# ProSense.net
KiCad netlist of a schematic drawn in EAGLE
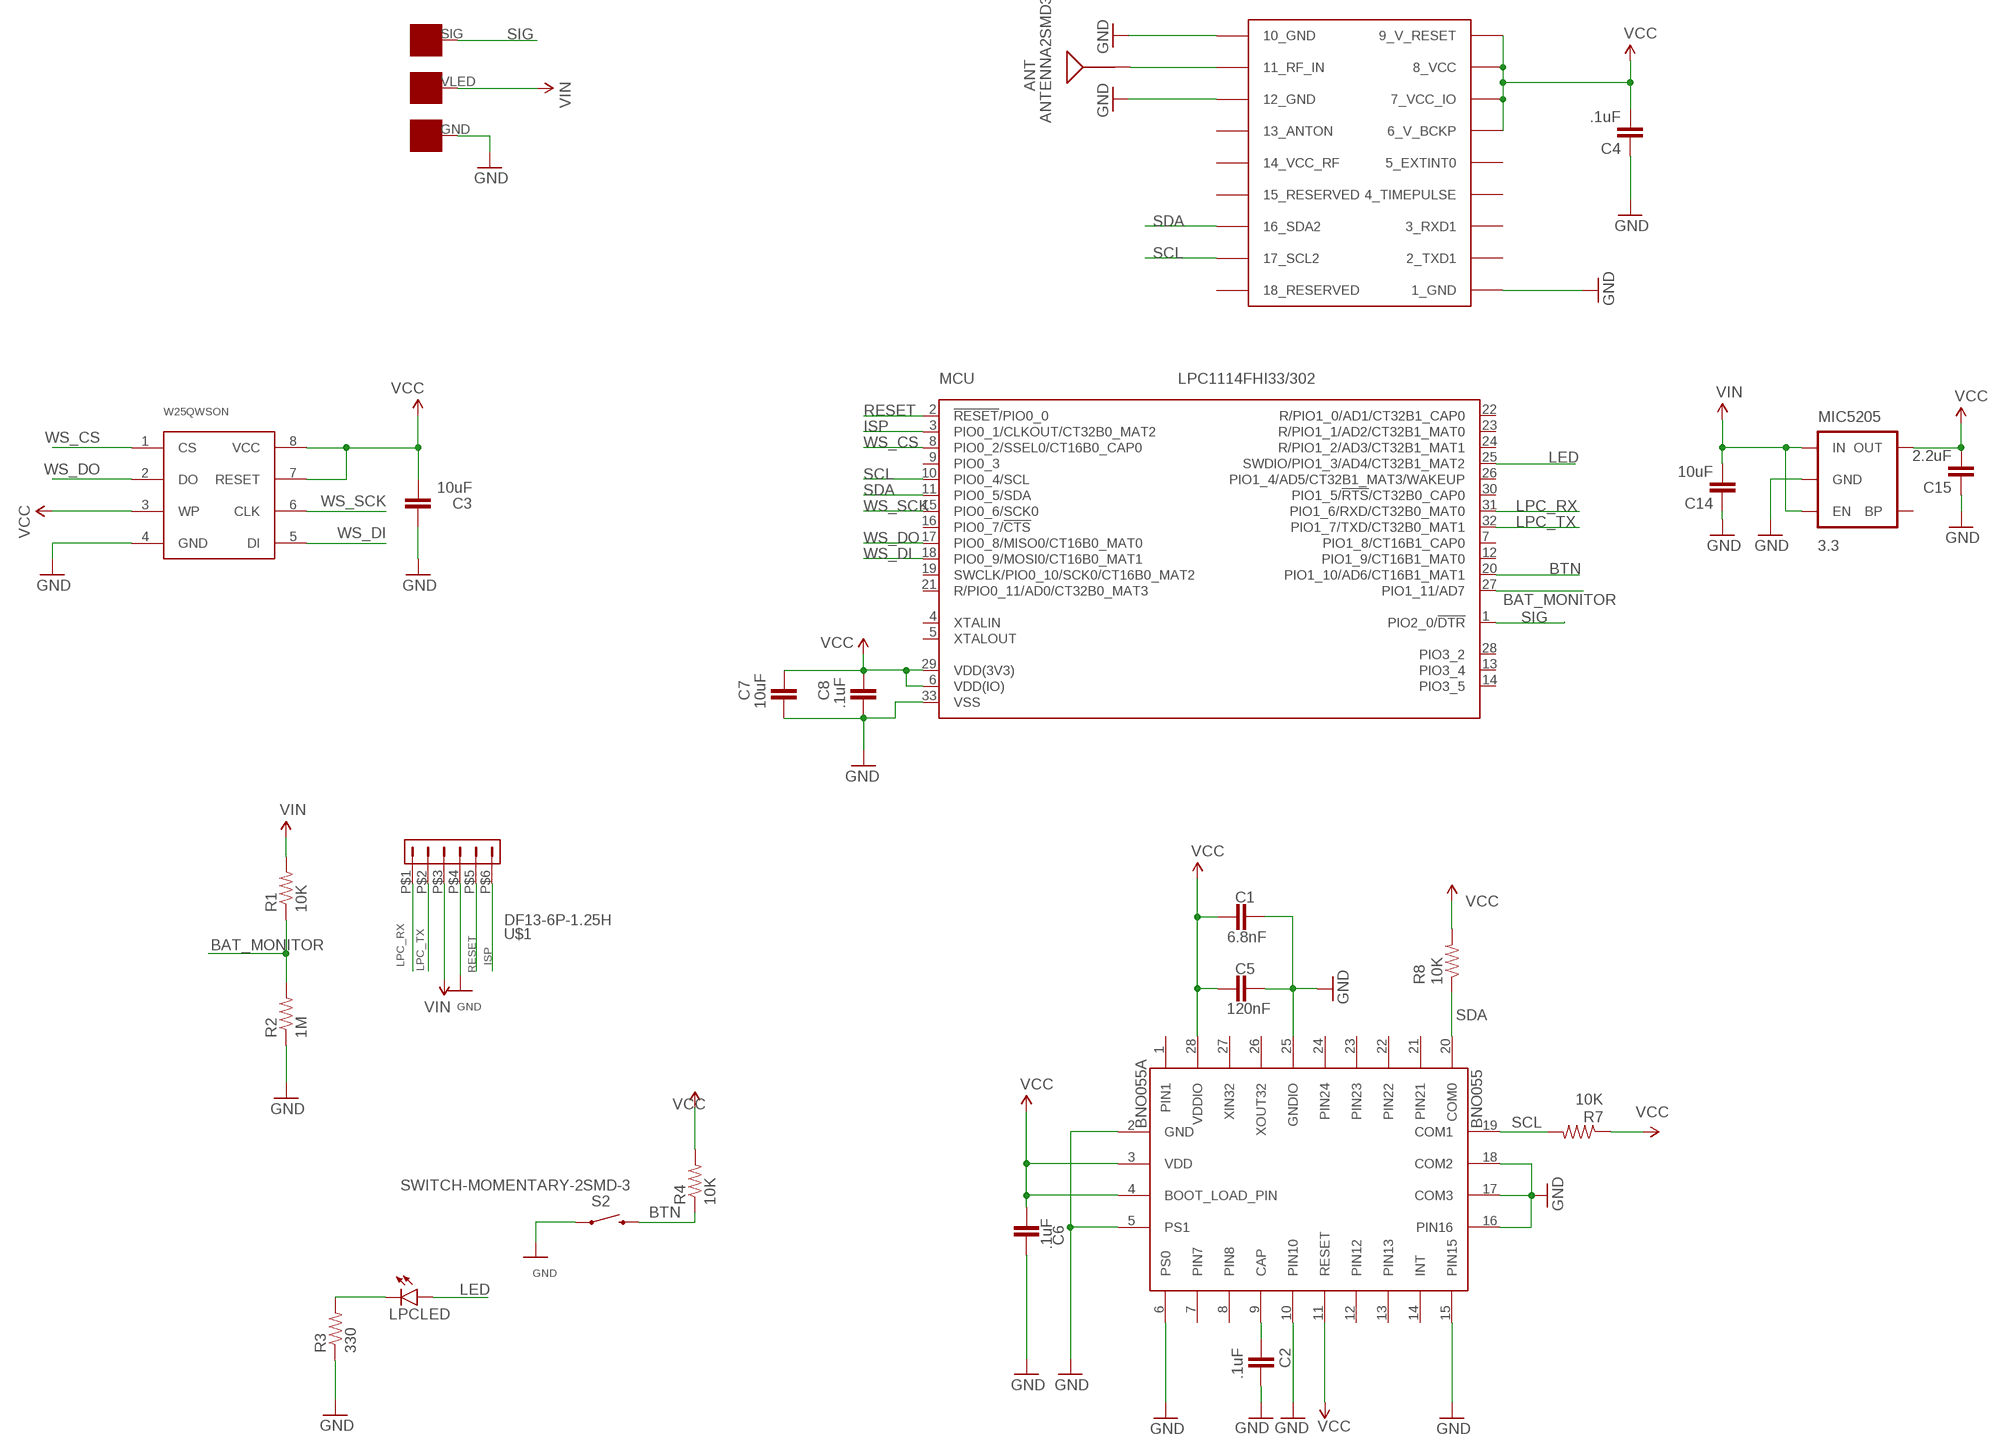
[diagram p0: schematic, sheet 1]

(export (version "E")
  (design (tool "Eeschema 10.0.6"))
  (components
    (comp (ref "ANT")
      (value "ANTENNA2SMD3")
      (footprint "eagle-import:ANTENNA-CHIP4")
      (libsource (lib "eagle-import") (part "ANTENNA2SMD3"))
    )
    (comp (ref "BNO055")
      (value "BNO055A")
      (footprint "eagle-import:BNO055")
      (libsource (lib "eagle-import") (part "BNO055A"))
    )
    (comp (ref "C1")
      (value "6.8nF")
      (footprint "eagle-import:0603-CAP")
      (libsource (lib "eagle-import") (part "CAP0603-CAP"))
    )
    (comp (ref "C2")
      (value ".1uF")
      (footprint "eagle-import:0603-CAP")
      (libsource (lib "eagle-import") (part "CAP0603-CAP"))
    )
    (comp (ref "C3")
      (value "10uF")
      (footprint "eagle-import:0603-CAP")
      (libsource (lib "eagle-import") (part "CAP0603-CAP"))
    )
    (comp (ref "C4")
      (value ".1uF")
      (footprint "eagle-import:0603-CAP")
      (libsource (lib "eagle-import") (part "CAP0603-CAP"))
    )
    (comp (ref "C5")
      (value "120nF")
      (footprint "eagle-import:0603-CAP")
      (libsource (lib "eagle-import") (part "CAP0603-CAP"))
    )
    (comp (ref "C6")
      (value ".1uF")
      (footprint "eagle-import:0603-CAP")
      (libsource (lib "eagle-import") (part "CAP0603-CAP"))
    )
    (comp (ref "C7")
      (value "10uF")
      (footprint "eagle-import:0603-CAP")
      (libsource (lib "eagle-import") (part "CAP0603-CAP"))
    )
    (comp (ref "C8")
      (value ".1uF")
      (footprint "eagle-import:0603-CAP")
      (libsource (lib "eagle-import") (part "CAP0603-CAP"))
    )
    (comp (ref "C14")
      (value "10uF")
      (footprint "eagle-import:0603-CAP")
      (libsource (lib "eagle-import") (part "CAP0603-CAP"))
    )
    (comp (ref "C15")
      (value "2.2uF")
      (footprint "eagle-import:0603-CAP")
      (libsource (lib "eagle-import") (part "CAP0603-CAP"))
    )
    (comp (ref "LPCLED")
      (value "LED0603")
      (footprint "eagle-import:LED-0603")
      (libsource (lib "eagle-import") (part "LED0603"))
    )
    (comp (ref "MCU")
      (value "LPC1114FHI33/302")
      (footprint "eagle-import:SOT617-3")
      (libsource (lib "eagle-import") (part "LPC1114FHI33/302"))
    )
    (comp (ref "MIC5205")
      (value "3.3")
      (footprint "eagle-import:SOT23-5")
      (libsource (lib "eagle-import") (part "MIC52053.3V"))
    )
    (comp (ref "R1")
      (value "10K")
      (footprint "eagle-import:0603-RES")
      (libsource (lib "eagle-import") (part "RESISTOR0603-RES"))
    )
    (comp (ref "R2")
      (value "1M")
      (footprint "eagle-import:0603-RES")
      (libsource (lib "eagle-import") (part "RESISTOR0603-RES"))
    )
    (comp (ref "R3")
      (value "330")
      (footprint "eagle-import:0603-RES")
      (libsource (lib "eagle-import") (part "RESISTOR0603-RES"))
    )
    (comp (ref "R4")
      (value "10K")
      (footprint "eagle-import:0603-RES")
      (libsource (lib "eagle-import") (part "RESISTOR0603-RES"))
    )
    (comp (ref "R7")
      (value "10K")
      (footprint "eagle-import:0603-RES")
      (libsource (lib "eagle-import") (part "RESISTOR0603-RES"))
    )
    (comp (ref "R8")
      (value "10K")
      (footprint "eagle-import:0603-RES")
      (libsource (lib "eagle-import") (part "RESISTOR0603-RES"))
    )
    (comp (ref "S2")
      (value "SWITCH-MOMENTARY-2SMD-3")
      (footprint "eagle-import:TACTILE_SWITCH_SMD-3")
      (libsource (lib "eagle-import") (part "SWITCH-MOMENTARY-2SMD-3"))
    )
    (comp (ref "U$1")
      (value "DF13-6P-1.25H")
      (footprint "eagle-import:DF13A-6P-1.25H")
      (libsource (lib "eagle-import") (part "DF13-6P-1.25H"))
    )
    (comp (ref "U$2")
      (value "UBLOX_MAX")
      (footprint "eagle-import:UBLOX_MAX")
      (libsource (lib "eagle-import") (part "UBLOX_MAX"))
    )
    (comp (ref "U$4")
      (value "CON")
      (footprint "eagle-import:COPPER-PAD")
      (libsource (lib "eagle-import") (part "CON"))
    )
    (comp (ref "W25QWSON")
      (value "W25Q128FVWSON")
      (footprint "eagle-import:WSON-8-PAD")
      (libsource (lib "eagle-import") (part "W25Q128FVWSON"))
    )
  )
  (nets
    (net (code "1") (name "/BAT_MONITOR") (class "Default")
      (node (ref "MCU") (pin "27") (pinfunction "PIO1_11/AD7_27") (pintype "bidirectional"))
      (node (ref "R1") (pin "1") (pinfunction "1_1") (pintype "passive"))
      (node (ref "R2") (pin "2") (pinfunction "2_2") (pintype "passive"))
    )
    (net (code "2") (name "/BTN") (class "Default")
      (node (ref "MCU") (pin "20") (pinfunction "PIO1_10/AD6/CT16B1_MAT1_20") (pintype "bidirectional"))
      (node (ref "R4") (pin "1") (pinfunction "1_1") (pintype "passive"))
      (node (ref "S2") (pin "4") (pinfunction "2_4") (pintype "passive"))
    )
    (net (code "3") (name "/ISP") (class "Default")
      (node (ref "MCU") (pin "3") (pinfunction "PIO0_1/CLKOUT/CT32B0_MAT2_3") (pintype "bidirectional"))
      (node (ref "U$1") (pin "P$6") (pinfunction "6_P$6") (pintype "passive"))
    )
    (net (code "4") (name "/LED") (class "Default")
      (node (ref "LPCLED") (pin "A") (pinfunction "A_A") (pintype "passive"))
      (node (ref "MCU") (pin "25") (pinfunction "SWDIO/PIO1_3/AD4/CT32B1_MAT2_25") (pintype "bidirectional"))
    )
    (net (code "5") (name "/LPC_RX") (class "Default")
      (node (ref "MCU") (pin "31") (pinfunction "PIO1_6/RXD/CT32B0_MAT0_31") (pintype "bidirectional"))
      (node (ref "U$1") (pin "P$1") (pinfunction "1_P$1") (pintype "passive"))
    )
    (net (code "6") (name "/LPC_TX") (class "Default")
      (node (ref "MCU") (pin "32") (pinfunction "PIO1_7/TXD/CT32B0_MAT1_32") (pintype "bidirectional"))
      (node (ref "U$1") (pin "P$2") (pinfunction "2_P$2") (pintype "passive"))
    )
    (net (code "7") (name "/RESET") (class "Default")
      (node (ref "MCU") (pin "2") (pinfunction "~{RESET}/PIO0_0_2") (pintype "bidirectional"))
      (node (ref "U$1") (pin "P$5") (pinfunction "5_P$5") (pintype "passive"))
    )
    (net (code "8") (name "/SCL") (class "Default")
      (node (ref "BNO055") (pin "19") (pinfunction "COM1_19") (pintype "bidirectional"))
      (node (ref "MCU") (pin "10") (pinfunction "PIO0_4/SCL_10") (pintype "bidirectional"))
      (node (ref "R7") (pin "2") (pinfunction "2_2") (pintype "passive"))
      (node (ref "U$2") (pin "17_SCL2") (pinfunction "17_SCL2_17_SCL2") (pintype "bidirectional"))
    )
    (net (code "9") (name "/SDA") (class "Default")
      (node (ref "BNO055") (pin "20") (pinfunction "COM0_20") (pintype "bidirectional"))
      (node (ref "MCU") (pin "11") (pinfunction "PIO0_5/SDA_11") (pintype "bidirectional"))
      (node (ref "R8") (pin "1") (pinfunction "1_1") (pintype "passive"))
      (node (ref "U$2") (pin "16_SDA2") (pinfunction "16_SDA2_16_SDA2") (pintype "bidirectional"))
    )
    (net (code "10") (name "/SIG") (class "Default")
      (node (ref "MCU") (pin "1") (pinfunction "PIO2_0/~{DTR}_1") (pintype "bidirectional"))
      (node (ref "U$4") (pin "SIG") (pinfunction "SIG_SIG") (pintype "bidirectional"))
    )
    (net (code "11") (name "/WS_CS") (class "Default")
      (node (ref "MCU") (pin "8") (pinfunction "PIO0_2/SSEL0/CT16B0_CAP0_8") (pintype "bidirectional"))
      (node (ref "W25QWSON") (pin "1") (pinfunction "CS_1") (pintype "input"))
    )
    (net (code "12") (name "/WS_DI") (class "Default")
      (node (ref "MCU") (pin "18") (pinfunction "PIO0_9/MOSI0/CT16B0_MAT1_18") (pintype "bidirectional"))
      (node (ref "W25QWSON") (pin "5") (pinfunction "DI_5") (pintype "input"))
    )
    (net (code "13") (name "/WS_DO") (class "Default")
      (node (ref "MCU") (pin "17") (pinfunction "PIO0_8/MISO0/CT16B0_MAT0_17") (pintype "bidirectional"))
      (node (ref "W25QWSON") (pin "2") (pinfunction "DO_2") (pintype "output"))
    )
    (net (code "14") (name "/WS_SCK") (class "Default")
      (node (ref "MCU") (pin "15") (pinfunction "PIO0_6/SCK0_15") (pintype "bidirectional"))
      (node (ref "W25QWSON") (pin "6") (pinfunction "CLK_6") (pintype "input"))
    )
    (net (code "15") (name "GND") (class "Default")
      (node (ref "BNO055") (pin "10") (pinfunction "PIN10_10") (pintype "bidirectional"))
      (node (ref "BNO055") (pin "15") (pinfunction "PIN15_15") (pintype "bidirectional"))
      (node (ref "BNO055") (pin "16") (pinfunction "PIN16_16") (pintype "bidirectional"))
      (node (ref "BNO055") (pin "17") (pinfunction "COM3_17") (pintype "bidirectional"))
      (node (ref "BNO055") (pin "18") (pinfunction "COM2_18") (pintype "bidirectional"))
      (node (ref "BNO055") (pin "2") (pinfunction "GND_2") (pintype "bidirectional"))
      (node (ref "BNO055") (pin "25") (pinfunction "GNDIO_25") (pintype "bidirectional"))
      (node (ref "BNO055") (pin "5") (pinfunction "PS1_5") (pintype "bidirectional"))
      (node (ref "BNO055") (pin "6") (pinfunction "PS0_6") (pintype "bidirectional"))
      (node (ref "C1") (pin "1") (pinfunction "1_1") (pintype "passive"))
      (node (ref "C14") (pin "1") (pinfunction "1_1") (pintype "passive"))
      (node (ref "C15") (pin "1") (pinfunction "1_1") (pintype "passive"))
      (node (ref "C2") (pin "1") (pinfunction "1_1") (pintype "passive"))
      (node (ref "C3") (pin "1") (pinfunction "1_1") (pintype "passive"))
      (node (ref "C4") (pin "1") (pinfunction "1_1") (pintype "passive"))
      (node (ref "C5") (pin "1") (pinfunction "1_1") (pintype "passive"))
      (node (ref "C6") (pin "2") (pinfunction "2_2") (pintype "passive"))
      (node (ref "C7") (pin "2") (pinfunction "2_2") (pintype "passive"))
      (node (ref "C8") (pin "2") (pinfunction "2_2") (pintype "passive"))
      (node (ref "MCU") (pin "33") (pinfunction "VSS_33") (pintype "power_in"))
      (node (ref "MIC5205") (pin "2") (pinfunction "GND_2") (pintype "input"))
      (node (ref "R2") (pin "1") (pinfunction "1_1") (pintype "passive"))
      (node (ref "R3") (pin "1") (pinfunction "1_1") (pintype "passive"))
      (node (ref "S2") (pin "1") (pinfunction "1_1") (pintype "passive"))
      (node (ref "U$1") (pin "P$4") (pinfunction "4_P$4") (pintype "passive"))
      (node (ref "U$2") (pin "10_GND") (pinfunction "10_GND_10_GND") (pintype "power_in"))
      (node (ref "U$2") (pin "12_GND") (pinfunction "12_GND_12_GND") (pintype "power_in"))
      (node (ref "U$2") (pin "1_GND") (pinfunction "1_GND_1_GND") (pintype "power_in"))
      (node (ref "U$4") (pin "GND") (pinfunction "GND_GND") (pintype "bidirectional"))
      (node (ref "W25QWSON") (pin "4") (pinfunction "GND_4") (pintype "power_in"))
    )
    (net (code "16") (name "Net-(ANT-SIGNAL)") (class "Default")
      (node (ref "ANT") (pin "SIG") (pinfunction "SIGNAL_SIG") (pintype "bidirectional"))
      (node (ref "U$2") (pin "11_RF_IN") (pinfunction "11_RF_IN_11_RF_IN") (pintype "bidirectional"))
    )
    (net (code "17") (name "Net-(BNO055-CAP)") (class "Default")
      (node (ref "BNO055") (pin "9") (pinfunction "CAP_9") (pintype "bidirectional"))
      (node (ref "C2") (pin "2") (pinfunction "2_2") (pintype "passive"))
    )
    (net (code "18") (name "Net-(LPCLED-PadC)") (class "Default")
      (node (ref "LPCLED") (pin "C") (pinfunction "C_C") (pintype "passive"))
      (node (ref "R3") (pin "2") (pinfunction "2_2") (pintype "passive"))
    )
    (net (code "19") (name "VCC") (class "Default")
      (node (ref "BNO055") (pin "11") (pinfunction "RESET_11") (pintype "bidirectional"))
      (node (ref "BNO055") (pin "28") (pinfunction "VDDIO_28") (pintype "bidirectional"))
      (node (ref "BNO055") (pin "3") (pinfunction "VDD_3") (pintype "bidirectional"))
      (node (ref "BNO055") (pin "4") (pinfunction "BOOT_LOAD_PIN_4") (pintype "bidirectional"))
      (node (ref "C1") (pin "2") (pinfunction "2_2") (pintype "passive"))
      (node (ref "C15") (pin "2") (pinfunction "2_2") (pintype "passive"))
      (node (ref "C3") (pin "2") (pinfunction "2_2") (pintype "passive"))
      (node (ref "C4") (pin "2") (pinfunction "2_2") (pintype "passive"))
      (node (ref "C5") (pin "2") (pinfunction "2_2") (pintype "passive"))
      (node (ref "C6") (pin "1") (pinfunction "1_1") (pintype "passive"))
      (node (ref "C7") (pin "1") (pinfunction "1_1") (pintype "passive"))
      (node (ref "C8") (pin "1") (pinfunction "1_1") (pintype "passive"))
      (node (ref "MCU") (pin "29") (pinfunction "VDD(3V3)_29") (pintype "power_in"))
      (node (ref "MCU") (pin "6") (pinfunction "VDD(IO)_6") (pintype "power_in"))
      (node (ref "MIC5205") (pin "5") (pinfunction "OUT_5") (pintype "passive"))
      (node (ref "R4") (pin "2") (pinfunction "2_2") (pintype "passive"))
      (node (ref "R7") (pin "1") (pinfunction "1_1") (pintype "passive"))
      (node (ref "R8") (pin "2") (pinfunction "2_2") (pintype "passive"))
      (node (ref "U$2") (pin "6_V_BCKP") (pinfunction "6_V_BCKP_6_V_BCKP") (pintype "bidirectional"))
      (node (ref "U$2") (pin "7_VCC_IO") (pinfunction "7_VCC_IO_7_VCC_IO") (pintype "power_in"))
      (node (ref "U$2") (pin "8_VCC") (pinfunction "8_VCC_8_VCC") (pintype "power_in"))
      (node (ref "U$2") (pin "9_V_RESET") (pinfunction "9_V_RESET_9_V_RESET") (pintype "power_in"))
      (node (ref "W25QWSON") (pin "3") (pinfunction "WP_3") (pintype "bidirectional"))
      (node (ref "W25QWSON") (pin "7") (pinfunction "RESET_7") (pintype "input"))
      (node (ref "W25QWSON") (pin "8") (pinfunction "VCC_8") (pintype "power_in"))
    )
    (net (code "20") (name "VIN") (class "Default")
      (node (ref "C14") (pin "2") (pinfunction "2_2") (pintype "passive"))
      (node (ref "MIC5205") (pin "1") (pinfunction "IN_1") (pintype "input"))
      (node (ref "MIC5205") (pin "3") (pinfunction "EN_3") (pintype "input"))
      (node (ref "R1") (pin "2") (pinfunction "2_2") (pintype "passive"))
      (node (ref "U$1") (pin "P$3") (pinfunction "3_P$3") (pintype "passive"))
      (node (ref "U$4") (pin "VLED") (pinfunction "VLED_VLED") (pintype "bidirectional"))
    )
    (net (code "21") (name "unconnected-(BNO055-INT-Pad14)") (class "Default")
      (node (ref "BNO055") (pin "14") (pinfunction "INT_14") (pintype "bidirectional"))
    )
    (net (code "22") (name "unconnected-(BNO055-PIN1-Pad1)") (class "Default")
      (node (ref "BNO055") (pin "1") (pinfunction "PIN1_1") (pintype "bidirectional"))
    )
    (net (code "23") (name "unconnected-(BNO055-PIN7-Pad7)") (class "Default")
      (node (ref "BNO055") (pin "7") (pinfunction "PIN7_7") (pintype "bidirectional"))
    )
    (net (code "24") (name "unconnected-(BNO055-PIN8-Pad8)") (class "Default")
      (node (ref "BNO055") (pin "8") (pinfunction "PIN8_8") (pintype "bidirectional"))
    )
    (net (code "25") (name "unconnected-(BNO055-PIN12-Pad12)") (class "Default")
      (node (ref "BNO055") (pin "12") (pinfunction "PIN12_12") (pintype "bidirectional"))
    )
    (net (code "26") (name "unconnected-(BNO055-PIN13-Pad13)") (class "Default")
      (node (ref "BNO055") (pin "13") (pinfunction "PIN13_13") (pintype "bidirectional"))
    )
    (net (code "27") (name "unconnected-(BNO055-PIN21-Pad21)") (class "Default")
      (node (ref "BNO055") (pin "21") (pinfunction "PIN21_21") (pintype "bidirectional"))
    )
    (net (code "28") (name "unconnected-(BNO055-PIN22-Pad22)") (class "Default")
      (node (ref "BNO055") (pin "22") (pinfunction "PIN22_22") (pintype "bidirectional"))
    )
    (net (code "29") (name "unconnected-(BNO055-PIN23-Pad23)") (class "Default")
      (node (ref "BNO055") (pin "23") (pinfunction "PIN23_23") (pintype "bidirectional"))
    )
    (net (code "30") (name "unconnected-(BNO055-PIN24-Pad24)") (class "Default")
      (node (ref "BNO055") (pin "24") (pinfunction "PIN24_24") (pintype "bidirectional"))
    )
    (net (code "31") (name "unconnected-(BNO055-XIN32-Pad27)") (class "Default")
      (node (ref "BNO055") (pin "27") (pinfunction "XIN32_27") (pintype "bidirectional"))
    )
    (net (code "32") (name "unconnected-(BNO055-XOUT32-Pad26)") (class "Default")
      (node (ref "BNO055") (pin "26") (pinfunction "XOUT32_26") (pintype "bidirectional"))
    )
    (net (code "33") (name "unconnected-(MCU-PIO0_3-Pad9)") (class "Default")
      (node (ref "MCU") (pin "9") (pinfunction "PIO0_3_9") (pintype "bidirectional"))
    )
    (net (code "34") (name "unconnected-(MCU-PIO0_7{slash}~{CTS}-Pad16)") (class "Default")
      (node (ref "MCU") (pin "16") (pinfunction "PIO0_7/~{CTS}_16") (pintype "bidirectional"))
    )
    (net (code "35") (name "unconnected-(MCU-PIO1_4{slash}AD5{slash}CT32B1_MAT3{slash}WAKEUP-Pad26)") (class "Default")
      (node (ref "MCU") (pin "26") (pinfunction "PIO1_4/AD5/CT32B1_MAT3/WAKEUP_26") (pintype "bidirectional"))
    )
    (net (code "36") (name "unconnected-(MCU-PIO1_5{slash}~{RTS}{slash}CT32B0_CAP0-Pad30)") (class "Default")
      (node (ref "MCU") (pin "30") (pinfunction "PIO1_5/~{RTS}/CT32B0_CAP0_30") (pintype "bidirectional"))
    )
    (net (code "37") (name "unconnected-(MCU-PIO1_8{slash}CT16B1_CAP0-Pad7)") (class "Default")
      (node (ref "MCU") (pin "7") (pinfunction "PIO1_8/CT16B1_CAP0_7") (pintype "bidirectional"))
    )
    (net (code "38") (name "unconnected-(MCU-PIO1_9{slash}CT16B1_MAT0-Pad12)") (class "Default")
      (node (ref "MCU") (pin "12") (pinfunction "PIO1_9/CT16B1_MAT0_12") (pintype "bidirectional"))
    )
    (net (code "39") (name "unconnected-(MCU-PIO3_2-Pad28)") (class "Default")
      (node (ref "MCU") (pin "28") (pinfunction "PIO3_2_28") (pintype "bidirectional"))
    )
    (net (code "40") (name "unconnected-(MCU-PIO3_4-Pad13)") (class "Default")
      (node (ref "MCU") (pin "13") (pinfunction "PIO3_4_13") (pintype "bidirectional"))
    )
    (net (code "41") (name "unconnected-(MCU-PIO3_5-Pad14)") (class "Default")
      (node (ref "MCU") (pin "14") (pinfunction "PIO3_5_14") (pintype "bidirectional"))
    )
    (net (code "42") (name "unconnected-(MCU-R{slash}PIO0_11{slash}AD0{slash}CT32B0_MAT3-Pad21)") (class "Default")
      (node (ref "MCU") (pin "21") (pinfunction "R/PIO0_11/AD0/CT32B0_MAT3_21") (pintype "bidirectional"))
    )
    (net (code "43") (name "unconnected-(MCU-R{slash}PIO1_0{slash}AD1{slash}CT32B1_CAP0-Pad22)") (class "Default")
      (node (ref "MCU") (pin "22") (pinfunction "R/PIO1_0/AD1/CT32B1_CAP0_22") (pintype "bidirectional"))
    )
    (net (code "44") (name "unconnected-(MCU-R{slash}PIO1_1{slash}AD2{slash}CT32B1_MAT0-Pad23)") (class "Default")
      (node (ref "MCU") (pin "23") (pinfunction "R/PIO1_1/AD2/CT32B1_MAT0_23") (pintype "bidirectional"))
    )
    (net (code "45") (name "unconnected-(MCU-R{slash}PIO1_2{slash}AD3{slash}CT32B1_MAT1-Pad24)") (class "Default")
      (node (ref "MCU") (pin "24") (pinfunction "R/PIO1_2/AD3/CT32B1_MAT1_24") (pintype "bidirectional"))
    )
    (net (code "46") (name "unconnected-(MCU-SWCLK{slash}PIO0_10{slash}SCK0{slash}CT16B0_MAT2-Pad19)") (class "Default")
      (node (ref "MCU") (pin "19") (pinfunction "SWCLK/PIO0_10/SCK0/CT16B0_MAT2_19") (pintype "bidirectional"))
    )
    (net (code "47") (name "unconnected-(MCU-XTALIN-Pad4)") (class "Default")
      (node (ref "MCU") (pin "4") (pinfunction "XTALIN_4") (pintype "input"))
    )
    (net (code "48") (name "unconnected-(MCU-XTALOUT-Pad5)") (class "Default")
      (node (ref "MCU") (pin "5") (pinfunction "XTALOUT_5") (pintype "output"))
    )
    (net (code "49") (name "unconnected-(MIC5205-BP-Pad4)") (class "Default")
      (node (ref "MIC5205") (pin "4") (pinfunction "BP_4") (pintype "input"))
    )
    (net (code "50") (name "unconnected-(U$2-Pad2_TXD1)") (class "Default")
      (node (ref "U$2") (pin "2_TXD1") (pinfunction "2_TXD1_2_TXD1") (pintype "bidirectional"))
    )
    (net (code "51") (name "unconnected-(U$2-Pad3_RXD1)") (class "Default")
      (node (ref "U$2") (pin "3_RXD1") (pinfunction "3_RXD1_3_RXD1") (pintype "bidirectional"))
    )
    (net (code "52") (name "unconnected-(U$2-Pad4_TIMEPULSE)") (class "Default")
      (node (ref "U$2") (pin "4_TIMEPULSE") (pinfunction "4_TIMEPULSE_4_TIMEPULSE") (pintype "bidirectional"))
    )
    (net (code "53") (name "unconnected-(U$2-Pad5_EXTINT0)") (class "Default")
      (node (ref "U$2") (pin "5_EXTINT0") (pinfunction "5_EXTINT0_5_EXTINT0") (pintype "bidirectional"))
    )
    (net (code "54") (name "unconnected-(U$2-Pad13_ANTON)") (class "Default")
      (node (ref "U$2") (pin "13_ANTON") (pinfunction "13_ANTON_13_ANTON") (pintype "bidirectional"))
    )
    (net (code "55") (name "unconnected-(U$2-Pad14_VCC_RF)") (class "Default")
      (node (ref "U$2") (pin "14_VCC_RF") (pinfunction "14_VCC_RF_14_VCC_RF") (pintype "bidirectional"))
    )
    (net (code "56") (name "unconnected-(U$2-Pad15_RESERVED)") (class "Default")
      (node (ref "U$2") (pin "15_RESERVED") (pinfunction "15_RESERVED_15_RESERVED") (pintype "bidirectional"))
    )
    (net (code "57") (name "unconnected-(U$2-Pad18_RESERVED)") (class "Default")
      (node (ref "U$2") (pin "18_RESERVED") (pinfunction "18_RESERVED_18_RESERVED") (pintype "bidirectional"))
    )
  )
)
